# 5VBulkhead.net
KiCad netlist of a schematic drawn in Altium Designer
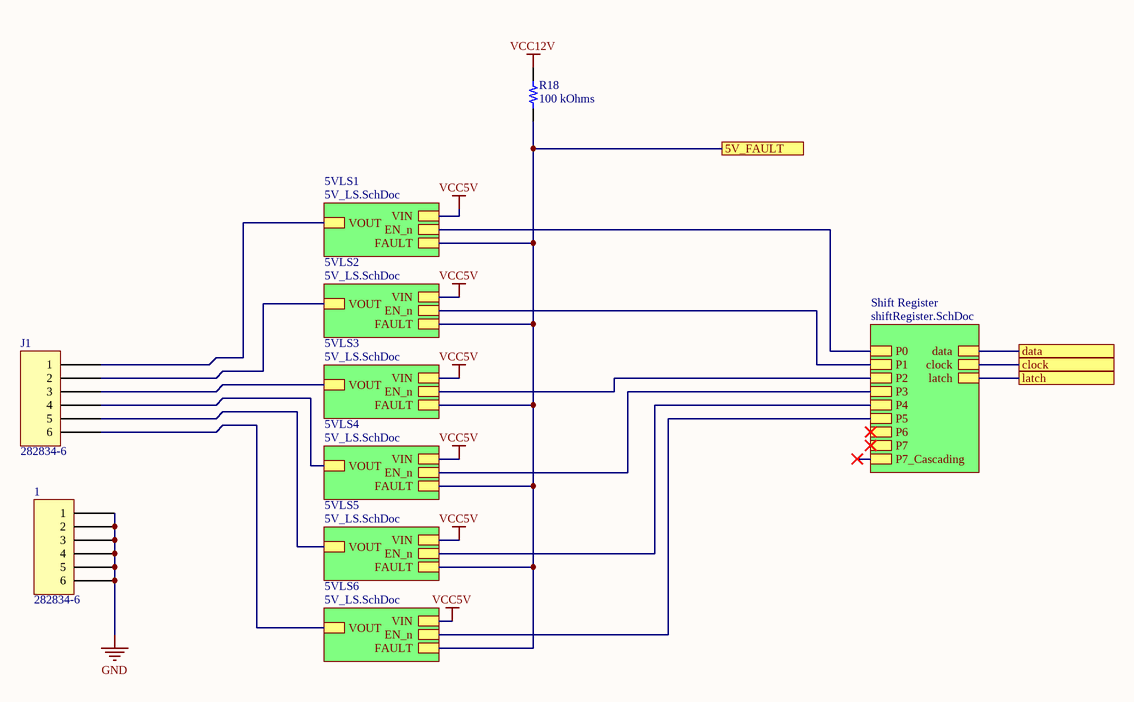
[diagram p0: 5VBulkhead.SchDoc]

(export (version "E")
  (design (tool "Eeschema 10.0.6"))
  (components
    (comp (ref "1")
      (value "282834-6")
      (footprint "TE 282834-6")
      (description "TERM BLK 6P SIDE ENT 2.54MM PCB")
      (fields (field (name "MANUFACTURER") "TE Connectivity AMP Connectors") (field (name "VOLTAGE") "150V"))
      (libsource (lib "Celestial Altium Library - altium_library") (part "6 Pin"))
    )
    (comp (ref "J1")
      (value "282834-6")
      (footprint "TE 282834-6")
      (description "TERM BLK 6P SIDE ENT 2.54MM PCB")
      (fields (field (name "MANUFACTURER") "TE Connectivity AMP Connectors") (field (name "VOLTAGE") "150V"))
      (libsource (lib "Celestial Altium Library - altium_library") (part "6 Pin"))
    )
    (comp (ref "R18")
      (value "100 kOhms")
      (footprint "RES 0603_1608")
      (description "RES 100K OHM 0.1% 1/16W 0603")
      (fields
        (field (name "PART NUMBER") "RNCS0603BKE100K")
        (field (name "MANUFACTURER") "Stackpole Electronics Inc")
      )
      (libsource (lib "Celestial Altium Library - altium_library") (part "Resistor"))
    )
  )
  (nets
    (net (code "1") (name "/5V_FAULT") (class "Default")
      (node (ref "R18") (pin "1") (pinfunction "1_1") (pintype "passive"))
    )
    (net (code "11") (name "/VOUT") (class "Default")
      (node (ref "J1") (pin "1") (pinfunction "1_1") (pintype "passive"))
    )
    (net (code "12") (name "/VOUT_1") (class "Default")
      (node (ref "J1") (pin "4") (pinfunction "4_4") (pintype "passive"))
    )
    (net (code "13") (name "/VOUT_2") (class "Default")
      (node (ref "J1") (pin "3") (pinfunction "3_3") (pintype "passive"))
    )
    (net (code "14") (name "/VOUT_3") (class "Default")
      (node (ref "J1") (pin "5") (pinfunction "5_5") (pintype "passive"))
    )
    (net (code "15") (name "/VOUT_4") (class "Default")
      (node (ref "J1") (pin "6") (pinfunction "6_6") (pintype "passive"))
    )
    (net (code "16") (name "/VOUT_5") (class "Default")
      (node (ref "J1") (pin "2") (pinfunction "2_2") (pintype "passive"))
    )
    (net (code "20") (name "GND") (class "Default")
      (node (ref "1") (pin "1") (pinfunction "1_1") (pintype "passive"))
      (node (ref "1") (pin "2") (pinfunction "2_2") (pintype "passive"))
      (node (ref "1") (pin "3") (pinfunction "3_3") (pintype "passive"))
      (node (ref "1") (pin "4") (pinfunction "4_4") (pintype "passive"))
      (node (ref "1") (pin "5") (pinfunction "5_5") (pintype "passive"))
      (node (ref "1") (pin "6") (pinfunction "6_6") (pintype "passive"))
    )
    (net (code "22") (name "VCC12V") (class "Default")
      (node (ref "R18") (pin "2") (pinfunction "2_2") (pintype "passive"))
    )
  )
)
